# Sheet1.net
KiCad netlist of a schematic drawn in Altium Designer
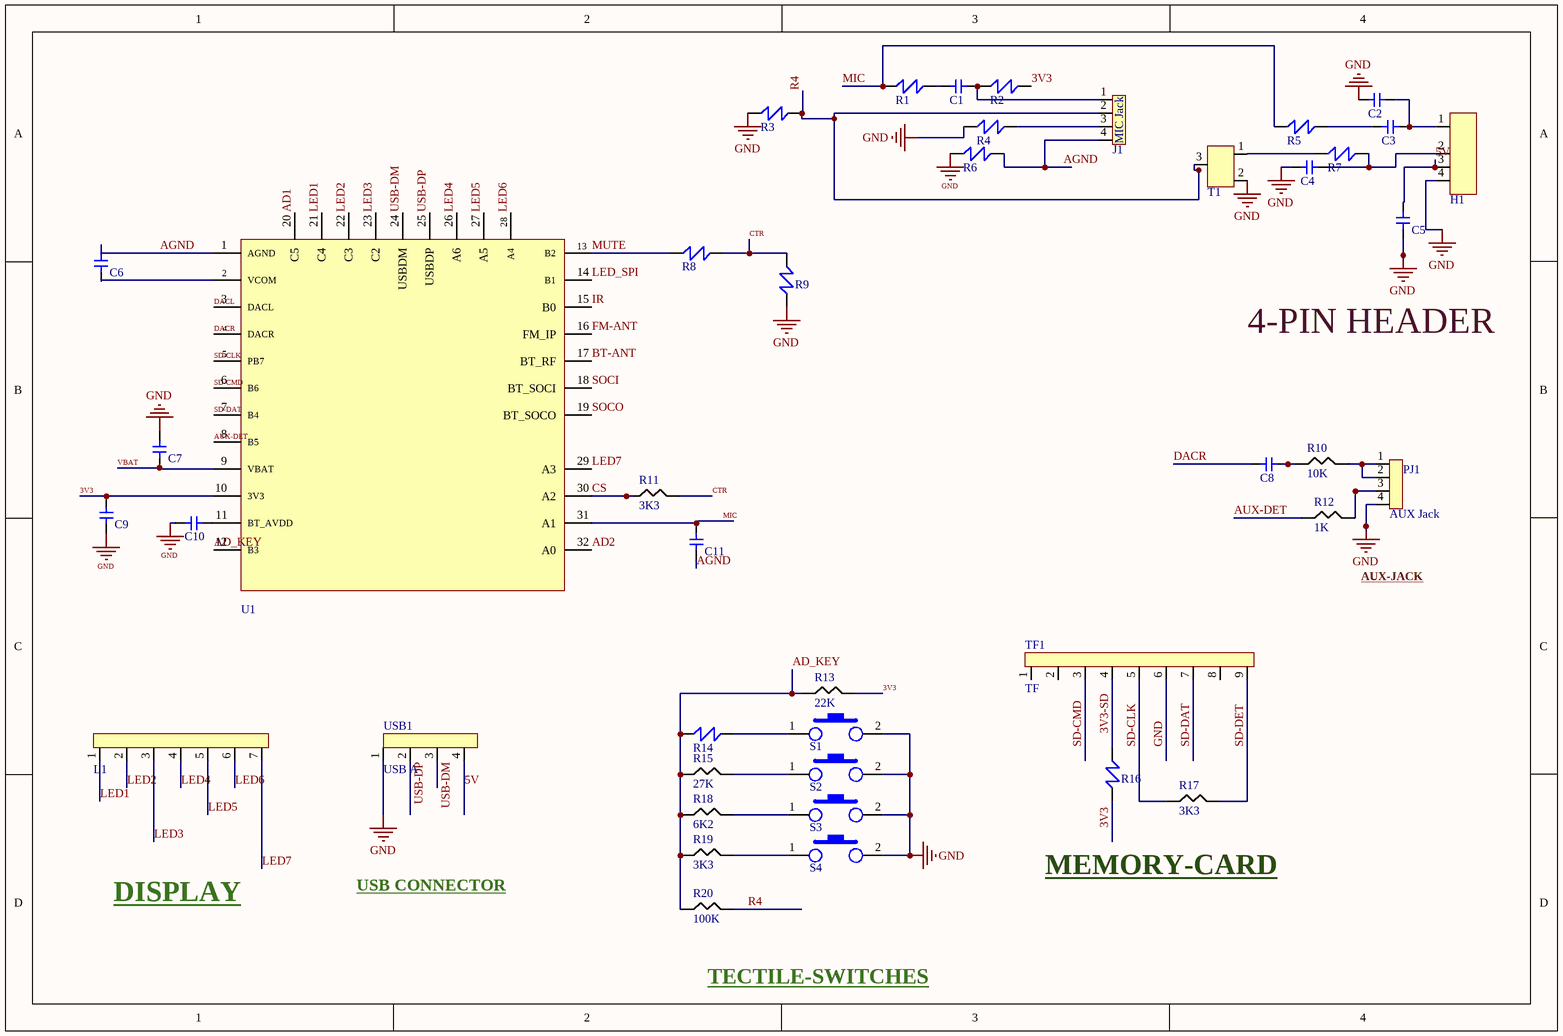
[diagram p0: Sheet1.SchDoc]

(export (version "E")
  (design (tool "Eeschema 10.0.6"))
  (components
    (comp (ref "C1")
      (value "220nF")
      (footprint "CAP 220nF")
      (description "220nf SMD Capcitor")
      (libsource (lib "Schlib1") (part "CAP_2"))
    )
    (comp (ref "C2")
      (value "10nf")
      (footprint "CAP 10nF")
      (description "10nf SMD Capcitor")
      (libsource (lib "Schlib1") (part "CAP_1"))
    )
    (comp (ref "C3")
      (value "220nF")
      (footprint "CAP 220nF")
      (description "220nf SMD Capcitor")
      (libsource (lib "Schlib1") (part "CAP_2"))
    )
    (comp (ref "C4")
      (value "100nF")
      (footprint "CAP 220nF")
      (description "100nf SMD Capcitor")
      (libsource (lib "Schlib1") (part "CAP_3"))
    )
    (comp (ref "C5")
      (value "1uF")
      (footprint "CAPM 1uF")
      (description "1uF SMD Capcitor")
      (libsource (lib "Schlib1") (part "CAP_4"))
    )
    (comp (ref "C6")
      (value "1uF")
      (footprint "CAP 10nF")
      (description "1uF SMD Capcitor")
      (libsource (lib "Schlib1") (part "CAP_4"))
    )
    (comp (ref "C7")
      (value "1uF")
      (footprint "CAP 10nF")
      (description "1uF SMD Capcitor")
      (libsource (lib "Schlib1") (part "CAP_4"))
    )
    (comp (ref "C8")
      (value "1uF")
      (footprint "CAPM 1uF")
      (description "1uF SMD Capcitor")
      (libsource (lib "Schlib1") (part "CAP_4"))
    )
    (comp (ref "C9")
      (value "1uF")
      (footprint "CAP 10nF")
      (description "1uF SMD Capcitor")
      (libsource (lib "Schlib1") (part "CAP_4"))
    )
    (comp (ref "C10")
      (value "1uF")
      (footprint "CAP 10nF")
      (description "1uF SMD Capcitor")
      (libsource (lib "Schlib1") (part "CAP_4"))
    )
    (comp (ref "C11")
      (value "10uF")
      (footprint "CAP 10nF")
      (description "10uF SMD Capcitor")
      (libsource (lib "Schlib1") (part "CAP_5"))
    )
    (comp (ref "H1")
      (value "HEADER")
      (footprint "Header4")
      (description "4PIN HEADER")
      (libsource (lib "Schlib1") (part "HEADER"))
    )
    (comp (ref "J1") (value "MIC Jack") (footprint "MIC") (libsource (lib "Schlib1") (part "MIC")))
    (comp (ref "L1")
      (value "LED_DISPLAY_3308")
      (footprint "LED_DISPLAY_3308")
      (description "LED_DISPLAY/3308")
      (libsource (lib "Schlib1") (part "DISPLAY"))
    )
    (comp (ref "PJ1")
      (value "AUX Jack")
      (footprint "AUX")
      (description "AUX Jack, 3.5mm")
      (libsource (lib "Schlib1") (part "JACK 3.5MM"))
    )
    (comp (ref "R1")
      (value "4.7K")
      (footprint "R_4.7K")
      (description "4.7K SMD Resistance")
      (libsource (lib "Schlib1") (part "RES_1"))
    )
    (comp (ref "R2")
      (value "22K")
      (footprint "R_22K")
      (description "22K SMD Resistance")
      (libsource (lib "Schlib1") (part "RES"))
    )
    (comp (ref "R3") (value "NC") (footprint "R_NC") (libsource (lib "Schlib1") (part "RES_3")))
    (comp (ref "R4") (value "NC") (footprint "R_NC") (libsource (lib "Schlib1") (part "RES_3")))
    (comp (ref "R5")
      (value "4.7K")
      (footprint "R_4.7K")
      (description "4.7K SMD Resistance")
      (libsource (lib "Schlib1") (part "RES_1"))
    )
    (comp (ref "R6")
      (value "0R")
      (footprint "R_0")
      (description "0R SMD Resistance")
      (libsource (lib "Schlib1") (part "RES_4"))
    )
    (comp (ref "R7")
      (value "6k8")
      (footprint "R_22K")
      (description "6k8 SMD Resistance")
      (libsource (lib "Schlib1") (part "RES_2"))
    )
    (comp (ref "R8")
      (value "91K")
      (footprint "R_22K")
      (description "91K SMD Resistance")
      (libsource (lib "Schlib1") (part "RES_18"))
    )
    (comp (ref "R9")
      (value "68K")
      (footprint "R_22K")
      (description "68K SMD Resistance")
      (libsource (lib "Schlib1") (part "RES_17"))
    )
    (comp (ref "R10")
      (value "10K")
      (footprint "R_10K")
      (description "10K, SMD Resistance / 1% / 125mW / VISHAY")
      (libsource (lib "Schlib1") (part "RES_11"))
    )
    (comp (ref "R11")
      (value "3K3")
      (footprint "R_100K")
      (description "3K3, SMD Resistance / 1% / 125mW / VISHAY")
      (libsource (lib "Schlib1") (part "RES_7"))
    )
    (comp (ref "R12")
      (value "1K")
      (footprint "R_1K SECOND")
      (description "1K, SMD Resistance / 1% / 125mW / VISHAY")
      (libsource (lib "Schlib1") (part "RES_5"))
    )
    (comp (ref "R13")
      (value "22K")
      (footprint "R_22K")
      (description "22K, SMD Resistance / 1% / 125mW / VISHAY")
      (libsource (lib "Schlib1") (part "RES_10"))
    )
    (comp (ref "R14")
      (value "0R")
      (footprint "R_0")
      (description "0R SMD Resistance")
      (libsource (lib "Schlib1") (part "RES_4"))
    )
    (comp (ref "R15")
      (value "27K")
      (footprint "R_27K")
      (description "27K, SMD Resistance / 1% / 125mW / VISHAY")
      (libsource (lib "Schlib1") (part "RES_9"))
    )
    (comp (ref "R16")
      (value "4.7K")
      (footprint "R_4.7K")
      (description "4.7K SMD Resistance")
      (libsource (lib "Schlib1") (part "RES_1"))
    )
    (comp (ref "R17")
      (value "3K3")
      (footprint "R_100K")
      (description "3K3, SMD Resistance / 1% / 125mW / VISHAY")
      (libsource (lib "Schlib1") (part "RES_7"))
    )
    (comp (ref "R18")
      (value "6K2")
      (footprint "R_6K2")
      (description "6K2, SMD Resistance / 1% / 125mW / VISHAY")
      (libsource (lib "Schlib1") (part "RES_8"))
    )
    (comp (ref "R19")
      (value "3K3")
      (footprint "R_100K")
      (description "3K3, SMD Resistance / 1% / 125mW / VISHAY")
      (libsource (lib "Schlib1") (part "RES_7"))
    )
    (comp (ref "R20")
      (value "100K")
      (footprint "R_100K")
      (description "100K, SMD Resistance / 1% / 125mW / VISHAY")
      (libsource (lib "Schlib1") (part "RES_6"))
    )
    (comp (ref "S1")
      (value "Teak switch")
      (footprint "teak switch")
      (description "Teak Switch")
      (libsource (lib "Schlib1") (part "Switch"))
    )
    (comp (ref "S2")
      (value "Teak switch")
      (footprint "teak switch")
      (description "Teak Switch")
      (libsource (lib "Schlib1") (part "Switch"))
    )
    (comp (ref "S3")
      (value "Teak switch")
      (footprint "teak switch")
      (description "Teak Switch")
      (libsource (lib "Schlib1") (part "Switch"))
    )
    (comp (ref "S4")
      (value "Teak switch")
      (footprint "teak switch")
      (description "Teak Switch")
      (libsource (lib "Schlib1") (part "Switch"))
    )
    (comp (ref "T1")
      (value "Transistor")
      (footprint "transisotr")
      (description "1AM")
      (libsource (lib "Schlib1") (part "Transistor"))
    )
    (comp (ref "TF1")
      (value "TF")
      (footprint "SD CARD")
      (description "TF Card, SD Card")
      (libsource (lib "Schlib1") (part "TF card"))
    )
    (comp (ref "U1") (value "AC6966") (footprint "AC6966") (libsource (lib "Schlib1") (part "AC6966")))
    (comp (ref "USB1") (value "USB A") (footprint "USB A") (libsource (lib "Schlib1") (part "USB")))
  )
  (nets
    (net (code "1") (name "/3V3") (class "Default")
      (node (ref "C9") (pin "2") (pinfunction "2_2") (pintype "passive"))
      (node (ref "R13") (pin "1") (pintype "passive"))
      (node (ref "R16") (pin "1") (pinfunction "1_1") (pintype "passive"))
      (node (ref "R2") (pin "2") (pinfunction "2_2") (pintype "passive"))
      (node (ref "U1") (pin "10") (pinfunction "3V3_10") (pintype "passive"))
    )
    (net (code "2") (name "/3V3-SD") (class "Default")
      (node (ref "R16") (pin "2") (pinfunction "2_2") (pintype "passive"))
      (node (ref "TF1") (pin "4") (pinfunction "4_4") (pintype "passive"))
    )
    (net (code "3") (name "/5V") (class "Default")
      (node (ref "C5") (pin "1") (pinfunction "1_1") (pintype "passive"))
      (node (ref "H1") (pin "3") (pinfunction "3_3") (pintype "passive"))
      (node (ref "USB1") (pin "4") (pinfunction "4_4") (pintype "passive"))
    )
    (net (code "5") (name "/AD1") (class "Default")
      (node (ref "U1") (pin "20") (pinfunction "C5_20") (pintype "passive"))
    )
    (net (code "6") (name "/AD2") (class "Default")
      (node (ref "U1") (pin "32") (pinfunction "A0_32") (pintype "passive"))
    )
    (net (code "7") (name "/AD_KEY") (class "Default")
      (node (ref "R13") (pin "2") (pintype "passive"))
      (node (ref "R14") (pin "1") (pinfunction "1_1") (pintype "passive"))
      (node (ref "R15") (pin "2") (pintype "passive"))
      (node (ref "R18") (pin "2") (pintype "passive"))
      (node (ref "R19") (pin "2") (pintype "passive"))
      (node (ref "R20") (pin "2") (pintype "passive"))
      (node (ref "U1") (pin "12") (pinfunction "B3_12") (pintype "passive"))
    )
    (net (code "8") (name "/AGND") (class "Default")
      (node (ref "C11") (pin "1") (pinfunction "1_1") (pintype "passive"))
      (node (ref "C6") (pin "2") (pinfunction "2_2") (pintype "passive"))
      (node (ref "J1") (pin "4") (pinfunction "4_4") (pintype "passive"))
      (node (ref "R6") (pin "2") (pinfunction "2_2") (pintype "passive"))
      (node (ref "U1") (pin "1") (pinfunction "AGND_1") (pintype "passive"))
    )
    (net (code "9") (name "/AUX-DET") (class "Default")
      (node (ref "R12") (pin "2") (pintype "passive"))
      (node (ref "U1") (pin "8") (pinfunction "B5_8") (pintype "passive"))
    )
    (net (code "10") (name "/BT-ANT") (class "Default")
      (node (ref "U1") (pin "17") (pinfunction "BT_RF_17") (pintype "passive"))
    )
    (net (code "11") (name "/CS") (class "Default")
      (node (ref "R11") (pin "2") (pintype "passive"))
      (node (ref "U1") (pin "30") (pinfunction "A2_30") (pintype "passive"))
    )
    (net (code "12") (name "/CTR") (class "Default")
      (node (ref "R11") (pin "1") (pintype "passive"))
      (node (ref "R8") (pin "2") (pinfunction "2_2") (pintype "passive"))
      (node (ref "R9") (pin "2") (pinfunction "2_2") (pintype "passive"))
    )
    (net (code "13") (name "/DACL") (class "Default")
      (node (ref "U1") (pin "3") (pinfunction "DACL_3") (pintype "passive"))
    )
    (net (code "14") (name "/DACR") (class "Default")
      (node (ref "C8") (pin "1") (pinfunction "1_1") (pintype "passive"))
      (node (ref "U1") (pin "4") (pinfunction "DACR_4") (pintype "passive"))
    )
    (net (code "15") (name "/FM-ANT") (class "Default")
      (node (ref "U1") (pin "16") (pinfunction "FM_IP_16") (pintype "passive"))
    )
    (net (code "16") (name "/IR") (class "Default")
      (node (ref "U1") (pin "15") (pinfunction "B0_15") (pintype "passive"))
    )
    (net (code "17") (name "/LED1") (class "Default")
      (node (ref "L1") (pin "1") (pinfunction "1_1") (pintype "passive"))
      (node (ref "U1") (pin "21") (pinfunction "C4_21") (pintype "passive"))
    )
    (net (code "18") (name "/LED2") (class "Default")
      (node (ref "L1") (pin "2") (pinfunction "2_2") (pintype "passive"))
      (node (ref "U1") (pin "22") (pinfunction "C3_22") (pintype "passive"))
    )
    (net (code "19") (name "/LED3") (class "Default")
      (node (ref "L1") (pin "3") (pinfunction "3_3") (pintype "passive"))
      (node (ref "U1") (pin "23") (pinfunction "C2_23") (pintype "passive"))
    )
    (net (code "20") (name "/LED4") (class "Default")
      (node (ref "L1") (pin "4") (pinfunction "4_4") (pintype "passive"))
      (node (ref "U1") (pin "26") (pinfunction "A6_26") (pintype "passive"))
    )
    (net (code "21") (name "/LED5") (class "Default")
      (node (ref "L1") (pin "5") (pinfunction "5_5") (pintype "passive"))
      (node (ref "U1") (pin "27") (pinfunction "A5_27") (pintype "passive"))
    )
    (net (code "22") (name "/LED6") (class "Default")
      (node (ref "L1") (pin "6") (pinfunction "6_6") (pintype "passive"))
      (node (ref "U1") (pin "28") (pinfunction "A4_28") (pintype "passive"))
    )
    (net (code "23") (name "/LED7") (class "Default")
      (node (ref "L1") (pin "7") (pinfunction "7_7") (pintype "passive"))
      (node (ref "U1") (pin "29") (pinfunction "A3_29") (pintype "passive"))
    )
    (net (code "24") (name "/LED_SPI") (class "Default")
      (node (ref "U1") (pin "14") (pinfunction "B1_14") (pintype "passive"))
    )
    (net (code "25") (name "/MIC") (class "Default")
      (node (ref "C11") (pin "2") (pinfunction "2_2") (pintype "passive"))
      (node (ref "R1") (pin "1") (pinfunction "1_1") (pintype "passive"))
      (node (ref "R5") (pin "1") (pinfunction "1_1") (pintype "passive"))
      (node (ref "U1") (pin "31") (pinfunction "A1_31") (pintype "passive"))
    )
    (net (code "26") (name "/MUTE") (class "Default")
      (node (ref "R8") (pin "1") (pinfunction "1_1") (pintype "passive"))
      (node (ref "U1") (pin "13") (pinfunction "B2_13") (pintype "passive"))
    )
    (net (code "27") (name "/R4") (class "Default")
      (node (ref "J1") (pin "2") (pinfunction "2_2") (pintype "passive"))
      (node (ref "R20") (pin "1") (pintype "passive"))
      (node (ref "R3") (pin "2") (pinfunction "2_2") (pintype "passive"))
      (node (ref "T1") (pin "3") (pinfunction "3_3") (pintype "passive"))
    )
    (net (code "28") (name "/SD-CLK") (class "Default")
      (node (ref "R17") (pin "2") (pintype "passive"))
      (node (ref "TF1") (pin "5") (pinfunction "5_5") (pintype "passive"))
      (node (ref "U1") (pin "5") (pinfunction "PB7_5") (pintype "passive"))
    )
    (net (code "29") (name "/SD-CMD") (class "Default")
      (node (ref "TF1") (pin "3") (pinfunction "3_3") (pintype "passive"))
      (node (ref "U1") (pin "6") (pinfunction "B6_6") (pintype "passive"))
    )
    (net (code "30") (name "/SD-DAT") (class "Default")
      (node (ref "TF1") (pin "7") (pinfunction "7_7") (pintype "passive"))
      (node (ref "U1") (pin "7") (pinfunction "B4_7") (pintype "passive"))
    )
    (net (code "31") (name "/SD-DET") (class "Default")
      (node (ref "R17") (pin "1") (pintype "passive"))
      (node (ref "TF1") (pin "9") (pinfunction "9_9") (pintype "passive"))
    )
    (net (code "32") (name "/SOCI") (class "Default")
      (node (ref "U1") (pin "18") (pinfunction "BT_SOCI_18") (pintype "passive"))
    )
    (net (code "33") (name "/SOCO") (class "Default")
      (node (ref "U1") (pin "19") (pinfunction "BT_SOCO_19") (pintype "passive"))
    )
    (net (code "34") (name "/USB-DM") (class "Default")
      (node (ref "U1") (pin "24") (pinfunction "USBDM_24") (pintype "passive"))
      (node (ref "USB1") (pin "3") (pinfunction "3_3") (pintype "passive"))
    )
    (net (code "35") (name "/USB-DP") (class "Default")
      (node (ref "U1") (pin "25") (pinfunction "USBDP_25") (pintype "passive"))
      (node (ref "USB1") (pin "2") (pinfunction "2_2") (pintype "passive"))
    )
    (net (code "36") (name "/VBAT") (class "Default")
      (node (ref "C7") (pin "1") (pinfunction "1_1") (pintype "passive"))
      (node (ref "U1") (pin "9") (pinfunction "VBAT_9") (pintype "passive"))
    )
    (net (code "37") (name "GND") (class "Default")
      (node (ref "C10") (pin "1") (pinfunction "1_1") (pintype "passive"))
      (node (ref "C2") (pin "1") (pinfunction "1_1") (pintype "passive"))
      (node (ref "C4") (pin "1") (pinfunction "1_1") (pintype "passive"))
      (node (ref "C5") (pin "2") (pinfunction "2_2") (pintype "passive"))
      (node (ref "C7") (pin "2") (pinfunction "2_2") (pintype "passive"))
      (node (ref "C9") (pin "1") (pinfunction "1_1") (pintype "passive"))
      (node (ref "H1") (pin "4") (pinfunction "4_4") (pintype "passive"))
      (node (ref "PJ1") (pin "4") (pinfunction "4_4") (pintype "passive"))
      (node (ref "R3") (pin "1") (pinfunction "1_1") (pintype "passive"))
      (node (ref "R4") (pin "1") (pinfunction "1_1") (pintype "passive"))
      (node (ref "R6") (pin "1") (pinfunction "1_1") (pintype "passive"))
      (node (ref "R9") (pin "1") (pinfunction "1_1") (pintype "passive"))
      (node (ref "S1") (pin "2") (pinfunction "2_2") (pintype "passive"))
      (node (ref "S2") (pin "2") (pinfunction "2_2") (pintype "passive"))
      (node (ref "S3") (pin "2") (pinfunction "2_2") (pintype "passive"))
      (node (ref "S4") (pin "2") (pinfunction "2_2") (pintype "passive"))
      (node (ref "T1") (pin "2") (pinfunction "2_2") (pintype "passive"))
      (node (ref "TF1") (pin "6") (pinfunction "6_6") (pintype "passive"))
      (node (ref "USB1") (pin "1") (pinfunction "1_1") (pintype "passive"))
    )
    (net (code "38") (name "Net-(C1-Pad1)") (class "Default")
      (node (ref "C1") (pin "1") (pinfunction "1_1") (pintype "passive"))
      (node (ref "R1") (pin "2") (pinfunction "2_2") (pintype "passive"))
    )
    (net (code "39") (name "Net-(C1-Pad2)") (class "Default")
      (node (ref "C1") (pin "2") (pinfunction "2_2") (pintype "passive"))
      (node (ref "J1") (pin "1") (pinfunction "1_1") (pintype "passive"))
      (node (ref "R2") (pin "1") (pinfunction "1_1") (pintype "passive"))
    )
    (net (code "40") (name "Net-(C2-Pad2)") (class "Default")
      (node (ref "C2") (pin "2") (pinfunction "2_2") (pintype "passive"))
      (node (ref "C3") (pin "2") (pinfunction "2_2") (pintype "passive"))
      (node (ref "H1") (pin "1") (pinfunction "1_1") (pintype "passive"))
    )
    (net (code "41") (name "Net-(C3-Pad1)") (class "Default")
      (node (ref "C3") (pin "1") (pinfunction "1_1") (pintype "passive"))
      (node (ref "R5") (pin "2") (pinfunction "2_2") (pintype "passive"))
    )
    (net (code "42") (name "Net-(C4-Pad2)") (class "Default")
      (node (ref "C4") (pin "2") (pinfunction "2_2") (pintype "passive"))
      (node (ref "H1") (pin "2") (pinfunction "2_2") (pintype "passive"))
      (node (ref "R7") (pin "2") (pinfunction "2_2") (pintype "passive"))
    )
    (net (code "43") (name "Net-(C8-Pad2)") (class "Default")
      (node (ref "C8") (pin "2") (pinfunction "2_2") (pintype "passive"))
      (node (ref "R10") (pin "2") (pintype "passive"))
    )
    (net (code "44") (name "Net-(J1-Pad3)") (class "Default")
      (node (ref "J1") (pin "3") (pinfunction "3_3") (pintype "passive"))
      (node (ref "R4") (pin "2") (pinfunction "2_2") (pintype "passive"))
    )
    (net (code "45") (name "Net-(PJ1-Pad1)") (class "Default")
      (node (ref "PJ1") (pin "1") (pinfunction "1_1") (pintype "passive"))
      (node (ref "PJ1") (pin "2") (pinfunction "2_2") (pintype "passive"))
      (node (ref "R10") (pin "1") (pintype "passive"))
    )
    (net (code "46") (name "Net-(PJ1-Pad3)") (class "Default")
      (node (ref "PJ1") (pin "3") (pinfunction "3_3") (pintype "passive"))
      (node (ref "R12") (pin "1") (pintype "passive"))
    )
    (net (code "47") (name "Net-(R7-Pad1)") (class "Default")
      (node (ref "R7") (pin "1") (pinfunction "1_1") (pintype "passive"))
      (node (ref "T1") (pin "1") (pinfunction "1_1") (pintype "passive"))
    )
    (net (code "48") (name "Net-(R14-Pad2)") (class "Default")
      (node (ref "R14") (pin "2") (pinfunction "2_2") (pintype "passive"))
      (node (ref "S1") (pin "1") (pinfunction "1_1") (pintype "passive"))
    )
    (net (code "49") (name "Net-(R15-Pad1)") (class "Default")
      (node (ref "R15") (pin "1") (pintype "passive"))
      (node (ref "S2") (pin "1") (pinfunction "1_1") (pintype "passive"))
    )
    (net (code "50") (name "Net-(R18-Pad1)") (class "Default")
      (node (ref "R18") (pin "1") (pintype "passive"))
      (node (ref "S3") (pin "1") (pinfunction "1_1") (pintype "passive"))
    )
    (net (code "51") (name "Net-(R19-Pad1)") (class "Default")
      (node (ref "R19") (pin "1") (pintype "passive"))
      (node (ref "S4") (pin "1") (pinfunction "1_1") (pintype "passive"))
    )
    (net (code "52") (name "Net-(U1-BT_AVDD)") (class "Default")
      (node (ref "C10") (pin "2") (pinfunction "2_2") (pintype "passive"))
      (node (ref "U1") (pin "11") (pinfunction "BT_AVDD_11") (pintype "passive"))
    )
    (net (code "53") (name "Net-(U1-VCOM)") (class "Default")
      (node (ref "C6") (pin "1") (pinfunction "1_1") (pintype "passive"))
      (node (ref "U1") (pin "2") (pinfunction "VCOM_2") (pintype "passive"))
    )
    (net (code "54") (name "unconnected-(TF1-Pad1)") (class "Default")
      (node (ref "TF1") (pin "1") (pinfunction "1_1") (pintype "passive"))
    )
    (net (code "55") (name "unconnected-(TF1-Pad2)") (class "Default")
      (node (ref "TF1") (pin "2") (pinfunction "2_2") (pintype "passive"))
    )
    (net (code "56") (name "unconnected-(TF1-Pad8)") (class "Default")
      (node (ref "TF1") (pin "8") (pinfunction "8_8") (pintype "passive"))
    )
  )
)
